# mainboard-schematic.net
KiCad netlist of a schematic drawn in Altium Designer
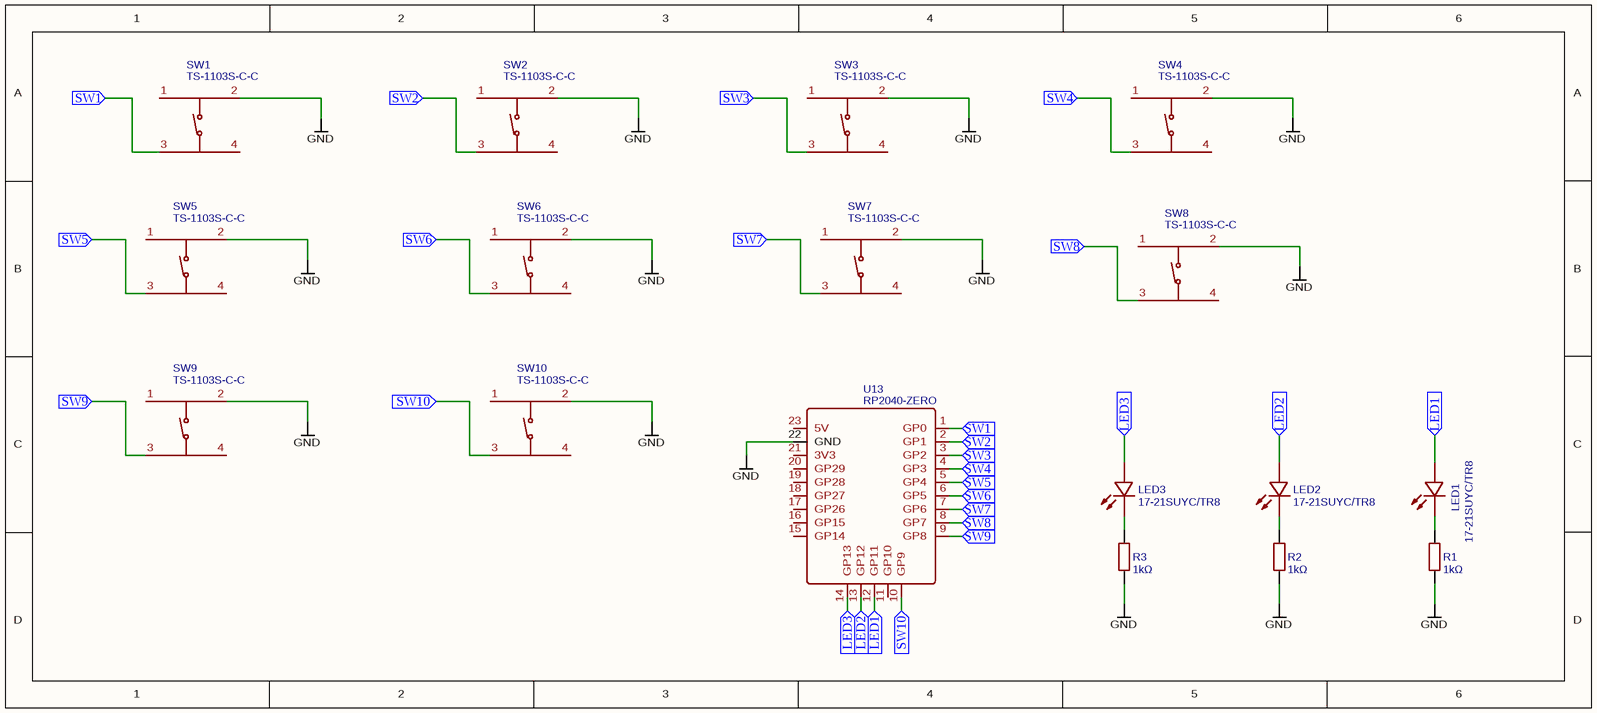
[diagram p0: mainboard-schematic.schdoc]

(export (version "E")
  (design (tool "Eeschema 10.0.6"))
  (components
    (comp (ref "LED1")
      (value "17-21SUYC/TR8")
      (fields (field (name "MANUFACTURER") "KENTO") (field (name "MANUFACTURER PART") "KT-0805黄灯"))
      (libsource (lib "altium-import") (part "root_1_17-21SUYC/TR8_"))
    )
    (comp (ref "LED2")
      (value "17-21SUYC/TR8")
      (fields (field (name "MANUFACTURER") "KENTO") (field (name "MANUFACTURER PART") "KT-0805黄灯"))
      (libsource (lib "altium-import") (part "root_1_17-21SUYC/TR8_"))
    )
    (comp (ref "LED3")
      (value "17-21SUYC/TR8")
      (fields (field (name "MANUFACTURER") "KENTO") (field (name "MANUFACTURER PART") "KT-0805黄灯"))
      (libsource (lib "altium-import") (part "root_1_17-21SUYC/TR8_"))
    )
    (comp (ref "R1")
      (value "1kΩ")
      (fields
        (field (name "MANUFACTURER") "UNI-ROYAL(厚声)")
        (field (name "MANUFACTURER PART") "1206W4F1001T5E")
      )
      (libsource (lib "altium-import") (part "root_3_1kΩ_"))
    )
    (comp (ref "R2")
      (value "1kΩ")
      (fields
        (field (name "MANUFACTURER") "UNI-ROYAL(厚声)")
        (field (name "MANUFACTURER PART") "1206W4F1001T5E")
      )
      (libsource (lib "altium-import") (part "root_3_1kΩ_"))
    )
    (comp (ref "R3")
      (value "1kΩ")
      (fields
        (field (name "MANUFACTURER") "UNI-ROYAL(厚声)")
        (field (name "MANUFACTURER PART") "1206W4F1001T5E")
      )
      (libsource (lib "altium-import") (part "root_3_1kΩ_"))
    )
    (comp (ref "SW1")
      (value "TS-1103S-C-C")
      (fields (field (name "MANUFACTURER") "XKB Connectivity(中国星坤)") (field (name "CONTRIBUTOR") "LCSC"))
      (libsource (lib "altium-import") (part "root_0_TS-1103S-C-C_"))
    )
    (comp (ref "SW2")
      (value "TS-1103S-C-C")
      (fields (field (name "MANUFACTURER") "XKB Connectivity(中国星坤)") (field (name "CONTRIBUTOR") "LCSC"))
      (libsource (lib "altium-import") (part "root_0_TS-1103S-C-C_"))
    )
    (comp (ref "SW3")
      (value "TS-1103S-C-C")
      (fields (field (name "MANUFACTURER") "XKB Connectivity(中国星坤)") (field (name "CONTRIBUTOR") "LCSC"))
      (libsource (lib "altium-import") (part "root_0_TS-1103S-C-C_"))
    )
    (comp (ref "SW4")
      (value "TS-1103S-C-C")
      (fields (field (name "MANUFACTURER") "XKB Connectivity(中国星坤)") (field (name "CONTRIBUTOR") "LCSC"))
      (libsource (lib "altium-import") (part "root_0_TS-1103S-C-C_"))
    )
    (comp (ref "SW5")
      (value "TS-1103S-C-C")
      (fields (field (name "MANUFACTURER") "XKB Connectivity(中国星坤)") (field (name "CONTRIBUTOR") "LCSC"))
      (libsource (lib "altium-import") (part "root_0_TS-1103S-C-C_"))
    )
    (comp (ref "SW6")
      (value "TS-1103S-C-C")
      (fields (field (name "MANUFACTURER") "XKB Connectivity(中国星坤)") (field (name "CONTRIBUTOR") "LCSC"))
      (libsource (lib "altium-import") (part "root_0_TS-1103S-C-C_"))
    )
    (comp (ref "SW7")
      (value "TS-1103S-C-C")
      (fields (field (name "MANUFACTURER") "XKB Connectivity(中国星坤)") (field (name "CONTRIBUTOR") "LCSC"))
      (libsource (lib "altium-import") (part "root_0_TS-1103S-C-C_"))
    )
    (comp (ref "SW8")
      (value "TS-1103S-C-C")
      (fields (field (name "MANUFACTURER") "XKB Connectivity(中国星坤)") (field (name "CONTRIBUTOR") "LCSC"))
      (libsource (lib "altium-import") (part "root_0_TS-1103S-C-C_"))
    )
    (comp (ref "SW9")
      (value "TS-1103S-C-C")
      (fields (field (name "MANUFACTURER") "XKB Connectivity(中国星坤)") (field (name "CONTRIBUTOR") "LCSC"))
      (libsource (lib "altium-import") (part "root_0_TS-1103S-C-C_"))
    )
    (comp (ref "SW10")
      (value "TS-1103S-C-C")
      (fields (field (name "MANUFACTURER") "XKB Connectivity(中国星坤)") (field (name "CONTRIBUTOR") "LCSC"))
      (libsource (lib "altium-import") (part "root_0_TS-1103S-C-C_"))
    )
    (comp (ref "U13")
      (value "RP2040-ZERO")
      (fields
        (field (name "MANUFACTURER") "Waveshare(微雪电子)")
        (field (name "MANUFACTURER PART") "RP2040-Zero")
        (field (name "CONTRIBUTOR") "lcsc")
      )
      (libsource (lib "altium-import") (part "root_0_RP2040-ZERO_"))
    )
  )
  (nets
    (net (code "1") (name "/LED1") (class "Default")
      (node (ref "LED1") (pin "1") (pinfunction "+_1") (pintype "passive"))
      (node (ref "U13") (pin "12") (pinfunction "GP11_12") (pintype "passive"))
    )
    (net (code "2") (name "/LED2") (class "Default")
      (node (ref "LED2") (pin "1") (pinfunction "+_1") (pintype "passive"))
      (node (ref "U13") (pin "13") (pinfunction "GP12_13") (pintype "passive"))
    )
    (net (code "3") (name "/LED3") (class "Default")
      (node (ref "LED3") (pin "1") (pinfunction "+_1") (pintype "passive"))
      (node (ref "U13") (pin "14") (pinfunction "GP13_14") (pintype "passive"))
    )
    (net (code "4") (name "/SW1") (class "Default")
      (node (ref "SW1") (pin "3") (pinfunction "3_3") (pintype "passive"))
      (node (ref "U13") (pin "1") (pinfunction "GP0_1") (pintype "passive"))
    )
    (net (code "5") (name "/SW2") (class "Default")
      (node (ref "SW2") (pin "3") (pinfunction "3_3") (pintype "passive"))
      (node (ref "U13") (pin "2") (pinfunction "GP1_2") (pintype "passive"))
    )
    (net (code "6") (name "/SW3") (class "Default")
      (node (ref "SW3") (pin "3") (pinfunction "3_3") (pintype "passive"))
      (node (ref "U13") (pin "3") (pinfunction "GP2_3") (pintype "passive"))
    )
    (net (code "7") (name "/SW4") (class "Default")
      (node (ref "SW4") (pin "3") (pinfunction "3_3") (pintype "passive"))
      (node (ref "U13") (pin "4") (pinfunction "GP3_4") (pintype "passive"))
    )
    (net (code "8") (name "/SW5") (class "Default")
      (node (ref "SW5") (pin "3") (pinfunction "3_3") (pintype "passive"))
      (node (ref "U13") (pin "5") (pinfunction "GP4_5") (pintype "passive"))
    )
    (net (code "9") (name "/SW6") (class "Default")
      (node (ref "SW6") (pin "3") (pinfunction "3_3") (pintype "passive"))
      (node (ref "U13") (pin "6") (pinfunction "GP5_6") (pintype "passive"))
    )
    (net (code "10") (name "/SW7") (class "Default")
      (node (ref "SW7") (pin "3") (pinfunction "3_3") (pintype "passive"))
      (node (ref "U13") (pin "7") (pinfunction "GP6_7") (pintype "passive"))
    )
    (net (code "11") (name "/SW8") (class "Default")
      (node (ref "SW8") (pin "3") (pinfunction "3_3") (pintype "passive"))
      (node (ref "U13") (pin "8") (pinfunction "GP7_8") (pintype "passive"))
    )
    (net (code "12") (name "/SW9") (class "Default")
      (node (ref "SW9") (pin "3") (pinfunction "3_3") (pintype "passive"))
      (node (ref "U13") (pin "9") (pinfunction "GP8_9") (pintype "passive"))
    )
    (net (code "13") (name "/SW10") (class "Default")
      (node (ref "SW10") (pin "3") (pinfunction "3_3") (pintype "passive"))
      (node (ref "U13") (pin "10") (pinfunction "GP9_10") (pintype "passive"))
    )
    (net (code "14") (name "GND") (class "Default")
      (node (ref "R1") (pin "2") (pinfunction "2_2") (pintype "passive"))
      (node (ref "R2") (pin "2") (pinfunction "2_2") (pintype "passive"))
      (node (ref "R3") (pin "2") (pinfunction "2_2") (pintype "passive"))
      (node (ref "SW1") (pin "2") (pinfunction "2_2") (pintype "passive"))
      (node (ref "SW10") (pin "2") (pinfunction "2_2") (pintype "passive"))
      (node (ref "SW2") (pin "2") (pinfunction "2_2") (pintype "passive"))
      (node (ref "SW3") (pin "2") (pinfunction "2_2") (pintype "passive"))
      (node (ref "SW4") (pin "2") (pinfunction "2_2") (pintype "passive"))
      (node (ref "SW5") (pin "2") (pinfunction "2_2") (pintype "passive"))
      (node (ref "SW6") (pin "2") (pinfunction "2_2") (pintype "passive"))
      (node (ref "SW7") (pin "2") (pinfunction "2_2") (pintype "passive"))
      (node (ref "SW8") (pin "2") (pinfunction "2_2") (pintype "passive"))
      (node (ref "SW9") (pin "2") (pinfunction "2_2") (pintype "passive"))
      (node (ref "U13") (pin "22") (pinfunction "GND_22") (pintype "passive"))
    )
    (net (code "15") (name "Net-(LED1--)") (class "Default")
      (node (ref "LED1") (pin "2") (pinfunction "-_2") (pintype "passive"))
      (node (ref "R1") (pin "1") (pinfunction "1_1") (pintype "passive"))
    )
    (net (code "16") (name "Net-(LED2--)") (class "Default")
      (node (ref "LED2") (pin "2") (pinfunction "-_2") (pintype "passive"))
      (node (ref "R2") (pin "1") (pinfunction "1_1") (pintype "passive"))
    )
    (net (code "17") (name "Net-(LED3--)") (class "Default")
      (node (ref "LED3") (pin "2") (pinfunction "-_2") (pintype "passive"))
      (node (ref "R3") (pin "1") (pinfunction "1_1") (pintype "passive"))
    )
    (net (code "18") (name "unconnected-(SW1-Pad1)") (class "Default")
      (node (ref "SW1") (pin "1") (pinfunction "1_1") (pintype "passive"))
    )
    (net (code "19") (name "unconnected-(SW1-Pad4)") (class "Default")
      (node (ref "SW1") (pin "4") (pinfunction "4_4") (pintype "passive"))
    )
    (net (code "20") (name "unconnected-(SW2-Pad1)") (class "Default")
      (node (ref "SW2") (pin "1") (pinfunction "1_1") (pintype "passive"))
    )
    (net (code "21") (name "unconnected-(SW2-Pad4)") (class "Default")
      (node (ref "SW2") (pin "4") (pinfunction "4_4") (pintype "passive"))
    )
    (net (code "22") (name "unconnected-(SW3-Pad1)") (class "Default")
      (node (ref "SW3") (pin "1") (pinfunction "1_1") (pintype "passive"))
    )
    (net (code "23") (name "unconnected-(SW3-Pad4)") (class "Default")
      (node (ref "SW3") (pin "4") (pinfunction "4_4") (pintype "passive"))
    )
    (net (code "24") (name "unconnected-(SW4-Pad1)") (class "Default")
      (node (ref "SW4") (pin "1") (pinfunction "1_1") (pintype "passive"))
    )
    (net (code "25") (name "unconnected-(SW4-Pad4)") (class "Default")
      (node (ref "SW4") (pin "4") (pinfunction "4_4") (pintype "passive"))
    )
    (net (code "26") (name "unconnected-(SW5-Pad1)") (class "Default")
      (node (ref "SW5") (pin "1") (pinfunction "1_1") (pintype "passive"))
    )
    (net (code "27") (name "unconnected-(SW5-Pad4)") (class "Default")
      (node (ref "SW5") (pin "4") (pinfunction "4_4") (pintype "passive"))
    )
    (net (code "28") (name "unconnected-(SW6-Pad1)") (class "Default")
      (node (ref "SW6") (pin "1") (pinfunction "1_1") (pintype "passive"))
    )
    (net (code "29") (name "unconnected-(SW6-Pad4)") (class "Default")
      (node (ref "SW6") (pin "4") (pinfunction "4_4") (pintype "passive"))
    )
    (net (code "30") (name "unconnected-(SW7-Pad1)") (class "Default")
      (node (ref "SW7") (pin "1") (pinfunction "1_1") (pintype "passive"))
    )
    (net (code "31") (name "unconnected-(SW7-Pad4)") (class "Default")
      (node (ref "SW7") (pin "4") (pinfunction "4_4") (pintype "passive"))
    )
    (net (code "32") (name "unconnected-(SW8-Pad1)") (class "Default")
      (node (ref "SW8") (pin "1") (pinfunction "1_1") (pintype "passive"))
    )
    (net (code "33") (name "unconnected-(SW8-Pad4)") (class "Default")
      (node (ref "SW8") (pin "4") (pinfunction "4_4") (pintype "passive"))
    )
    (net (code "34") (name "unconnected-(SW9-Pad1)") (class "Default")
      (node (ref "SW9") (pin "1") (pinfunction "1_1") (pintype "passive"))
    )
    (net (code "35") (name "unconnected-(SW9-Pad4)") (class "Default")
      (node (ref "SW9") (pin "4") (pinfunction "4_4") (pintype "passive"))
    )
    (net (code "36") (name "unconnected-(SW10-Pad1)") (class "Default")
      (node (ref "SW10") (pin "1") (pinfunction "1_1") (pintype "passive"))
    )
    (net (code "37") (name "unconnected-(SW10-Pad4)") (class "Default")
      (node (ref "SW10") (pin "4") (pinfunction "4_4") (pintype "passive"))
    )
    (net (code "38") (name "unconnected-(U13-3V3-Pad21)") (class "Default")
      (node (ref "U13") (pin "21") (pinfunction "3V3_21") (pintype "passive"))
    )
    (net (code "39") (name "unconnected-(U13-5V-Pad23)") (class "Default")
      (node (ref "U13") (pin "23") (pinfunction "5V_23") (pintype "passive"))
    )
    (net (code "40") (name "unconnected-(U13-GP10-Pad11)") (class "Default")
      (node (ref "U13") (pin "11") (pinfunction "GP10_11") (pintype "passive"))
    )
    (net (code "41") (name "unconnected-(U13-GP14-Pad15)") (class "Default")
      (node (ref "U13") (pin "15") (pinfunction "GP14_15") (pintype "passive"))
    )
    (net (code "42") (name "unconnected-(U13-GP15-Pad16)") (class "Default")
      (node (ref "U13") (pin "16") (pinfunction "GP15_16") (pintype "passive"))
    )
    (net (code "43") (name "unconnected-(U13-GP26-Pad17)") (class "Default")
      (node (ref "U13") (pin "17") (pinfunction "GP26_17") (pintype "passive"))
    )
    (net (code "44") (name "unconnected-(U13-GP27-Pad18)") (class "Default")
      (node (ref "U13") (pin "18") (pinfunction "GP27_18") (pintype "passive"))
    )
    (net (code "45") (name "unconnected-(U13-GP28-Pad19)") (class "Default")
      (node (ref "U13") (pin "19") (pinfunction "GP28_19") (pintype "passive"))
    )
    (net (code "46") (name "unconnected-(U13-GP29-Pad20)") (class "Default")
      (node (ref "U13") (pin "20") (pinfunction "GP29_20") (pintype "passive"))
    )
  )
)
